# board_1_5_FixMosfetGND_OUT12V_v.net
KiCad netlist of a schematic drawn in EAGLE
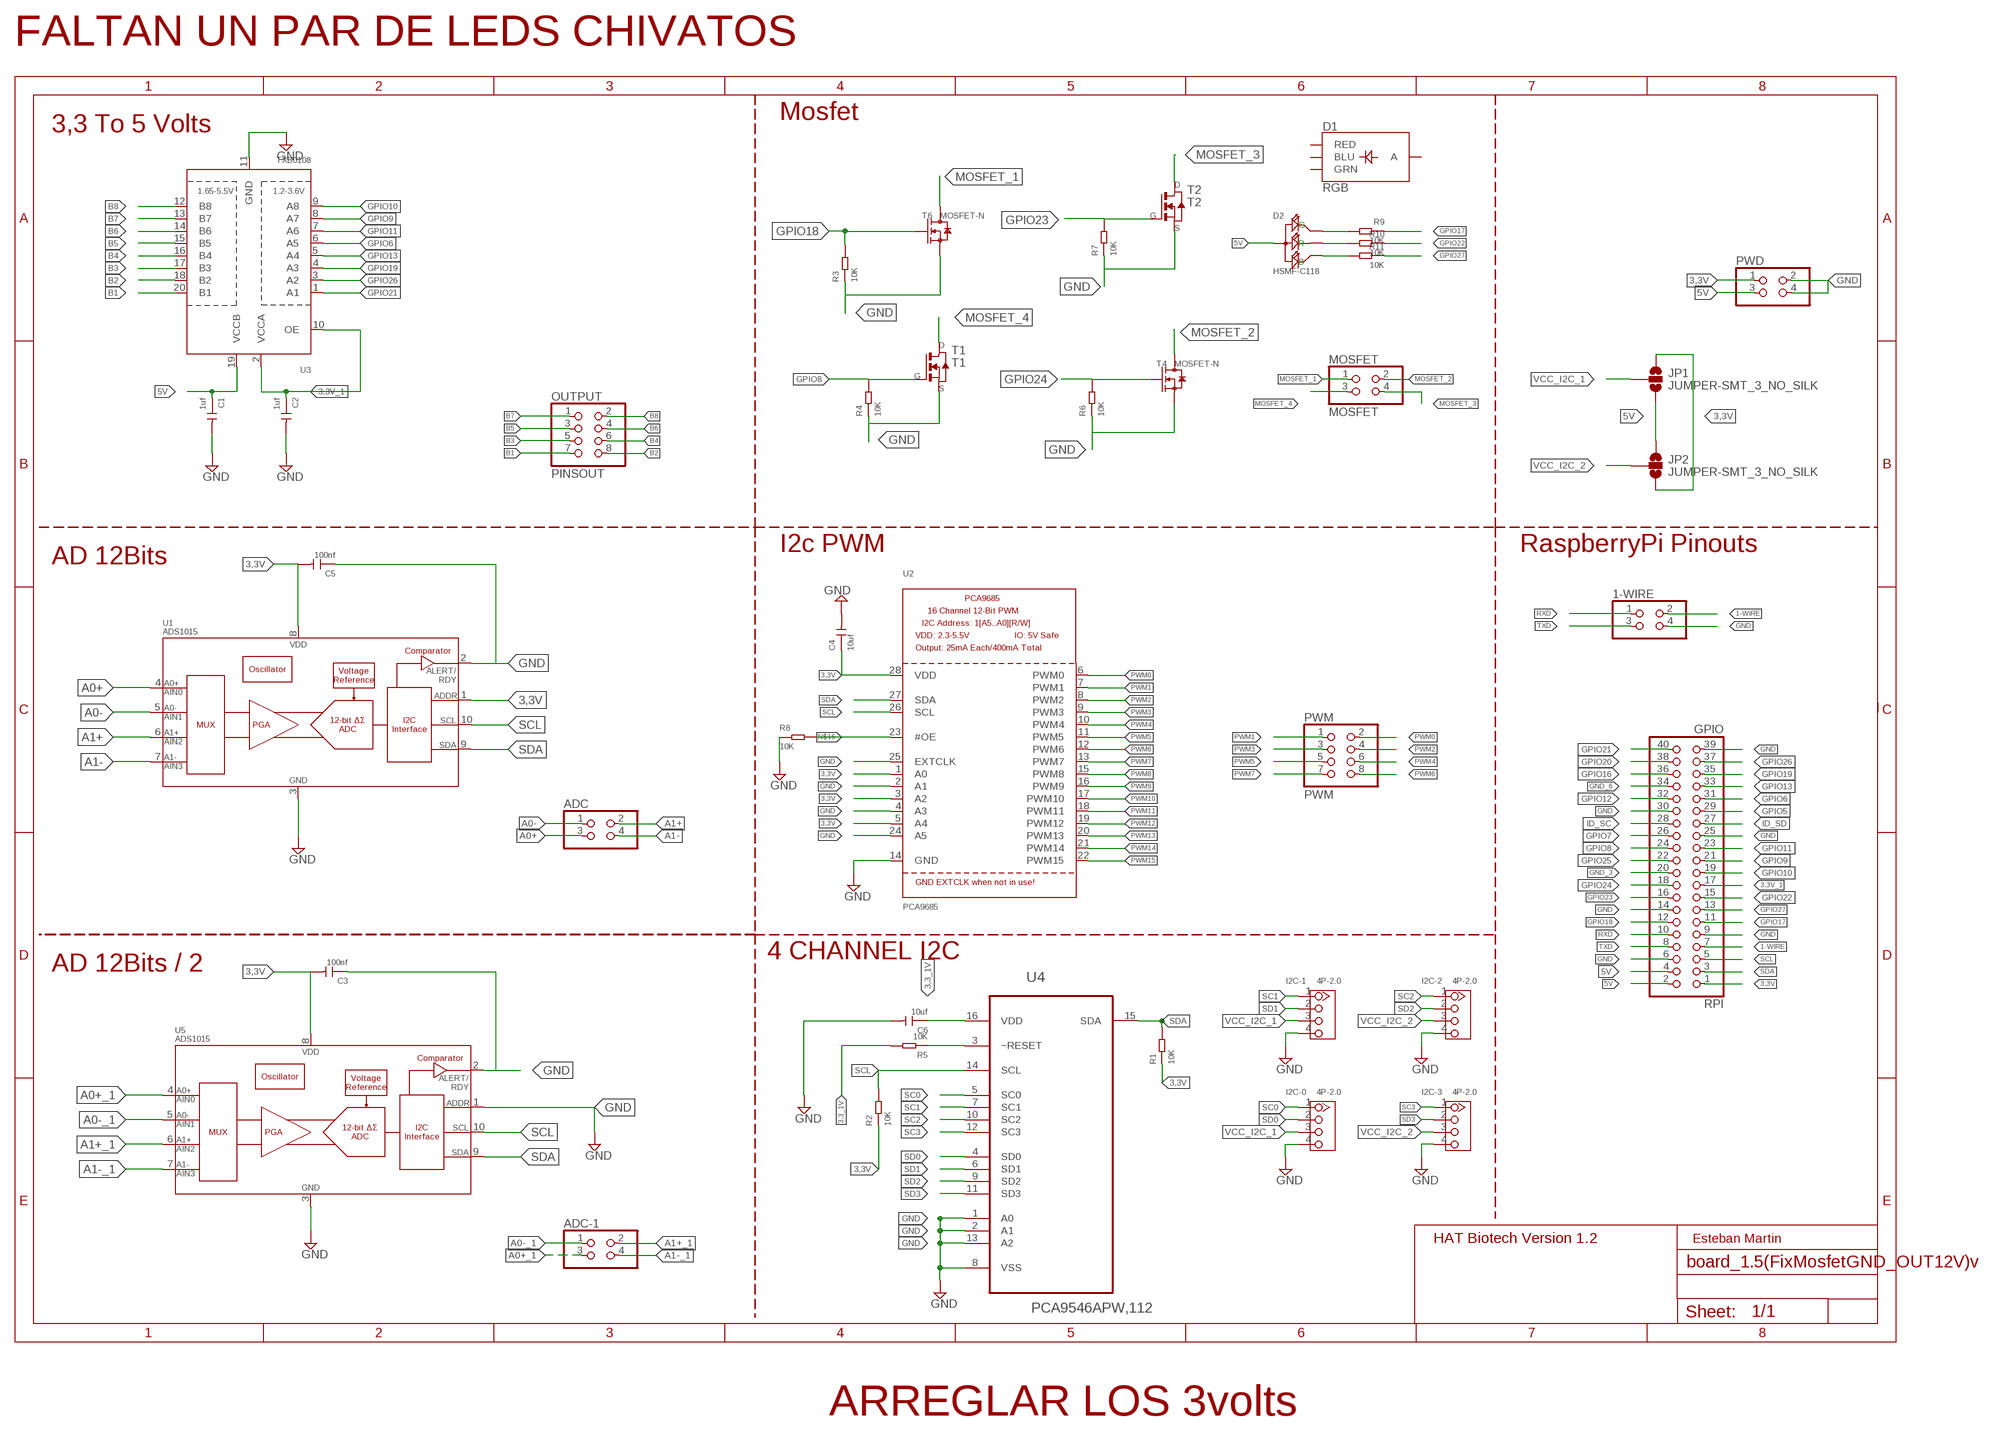
[diagram p0: schematic, sheet 1]

(export (version "E")
  (design (tool "Eeschema 10.0.6"))
  (components
    (comp (ref "1-WIRE")
      (value "PINHD-2X2")
      (footprint "eagle-import:2X02")
      (libsource (lib "eagle-import") (part "PINHD-2X2"))
    )
    (comp (ref "ADC")
      (value "PINHD-2X2")
      (footprint "eagle-import:2X02")
      (libsource (lib "eagle-import") (part "PINHD-2X2"))
    )
    (comp (ref "ADC-1")
      (value "PINHD-2X2")
      (footprint "eagle-import:2X02")
      (libsource (lib "eagle-import") (part "PINHD-2X2"))
    )
    (comp (ref "C1")
      (value "1uf")
      (footprint "eagle-import:C0805")
      (fields (field (name "MPN") "CC0805KKX7R8BB105"))
      (libsource (lib "eagle-import") (part "CERAMIC-1UF-25V-10%-X7R(0805)"))
    )
    (comp (ref "C2")
      (value "1uf")
      (footprint "eagle-import:C0805")
      (fields (field (name "MPN") "CC0805KKX7R8BB105"))
      (libsource (lib "eagle-import") (part "CERAMIC-1UF-25V-10%-X7R(0805)"))
    )
    (comp (ref "C3")
      (value "100nf")
      (footprint "eagle-import:C0805")
      (fields (field (name "MPN") "CC0805KRX7R9BB104"))
      (libsource (lib "eagle-import") (part "CERAMIC-100NF-50V-10%-X7R(0805)"))
    )
    (comp (ref "C4")
      (value "10uf")
      (footprint "eagle-import:C0805")
      (fields (field (name "MPN") "CC0805KKX7R8BB105"))
      (libsource (lib "eagle-import") (part "CERAMIC-1UF-25V-10%-X7R(0805)"))
    )
    (comp (ref "C5")
      (value "100nf")
      (footprint "eagle-import:C0805")
      (fields (field (name "MPN") "CC0805KRX7R9BB104"))
      (libsource (lib "eagle-import") (part "CERAMIC-100NF-50V-10%-X7R(0805)"))
    )
    (comp (ref "C6")
      (value "10uf")
      (footprint "eagle-import:C0805")
      (fields (field (name "MPN") "CC0805KKX7R8BB105"))
      (libsource (lib "eagle-import") (part "CERAMIC-1UF-25V-10%-X7R(0805)"))
    )
    (comp (ref "D1")
      (value "RGB")
      (footprint "eagle-import:P-LCC-4-3")
      (libsource (lib "eagle-import") (part "LED-RGB-CAPLCC"))
    )
    (comp (ref "D2")
      (value "HSMF-C118")
      (footprint "eagle-import:LED4-SMD-1210")
      (libsource (lib "eagle-import") (part "SMD-LED-RGB(4P-1210)"))
    )
    (comp (ref "I2C-0")
      (value "4P-2.0")
      (footprint "eagle-import:HW4-2.0")
      (libsource (lib "eagle-import") (part "GROVE-CONNECTOR-DIP(4P-2.0)"))
    )
    (comp (ref "I2C-1")
      (value "4P-2.0")
      (footprint "eagle-import:HW4-2.0")
      (libsource (lib "eagle-import") (part "GROVE-CONNECTOR-DIP(4P-2.0)"))
    )
    (comp (ref "I2C-2")
      (value "4P-2.0")
      (footprint "eagle-import:HW4-2.0")
      (libsource (lib "eagle-import") (part "GROVE-CONNECTOR-DIP(4P-2.0)"))
    )
    (comp (ref "I2C-3")
      (value "4P-2.0")
      (footprint "eagle-import:HW4-2.0")
      (libsource (lib "eagle-import") (part "GROVE-CONNECTOR-DIP(4P-2.0)"))
    )
    (comp (ref "JP1")
      (value "JUMPER-SMT_3_NO_SILK")
      (footprint "eagle-import:SMT-JUMPER_3_NO_SILK")
      (libsource (lib "eagle-import") (part "JUMPER-SMT_3_NO_SILK"))
    )
    (comp (ref "JP2")
      (value "JUMPER-SMT_3_NO_SILK")
      (footprint "eagle-import:SMT-JUMPER_3_NO_SILK")
      (libsource (lib "eagle-import") (part "JUMPER-SMT_3_NO_SILK"))
    )
    (comp (ref "MOSFET")
      (value "MOSFET")
      (footprint "eagle-import:2X02")
      (libsource (lib "eagle-import") (part "PINHD-2X2"))
    )
    (comp (ref "OUTPUT")
      (value "PINSOUT")
      (footprint "eagle-import:2X04")
      (libsource (lib "eagle-import") (part "PINHD-2X4"))
    )
    (comp (ref "PWD")
      (value "PINHD-2X2")
      (footprint "eagle-import:2X02")
      (libsource (lib "eagle-import") (part "PINHD-2X2"))
    )
    (comp (ref "PWM")
      (value "PWM")
      (footprint "eagle-import:2X04")
      (libsource (lib "eagle-import") (part "PINHD-2X4"))
    )
    (comp (ref "R1")
      (value "10K")
      (footprint "eagle-import:R0805")
      (fields (field (name "MPN") "RC0805FR-0710KL"))
      (libsource (lib "eagle-import") (part "SMD-RES-10K-1%-1/8W(0805)"))
    )
    (comp (ref "R2")
      (value "10K")
      (footprint "eagle-import:R0805")
      (fields (field (name "MPN") "RC0805FR-0710KL"))
      (libsource (lib "eagle-import") (part "SMD-RES-10K-1%-1/8W(0805)"))
    )
    (comp (ref "R3")
      (value "10K")
      (footprint "eagle-import:R0805")
      (fields (field (name "MPN") "RC0805FR-0710KL"))
      (libsource (lib "eagle-import") (part "SMD-RES-10K-1%-1/8W(0805)"))
    )
    (comp (ref "R4")
      (value "10K")
      (footprint "eagle-import:R0805")
      (fields (field (name "MPN") "RC0805FR-0710KL"))
      (libsource (lib "eagle-import") (part "SMD-RES-10K-1%-1/8W(0805)"))
    )
    (comp (ref "R5")
      (value "10K")
      (footprint "eagle-import:R0805")
      (fields (field (name "MPN") "RC0805FR-0710KL"))
      (libsource (lib "eagle-import") (part "SMD-RES-10K-1%-1/8W(0805)"))
    )
    (comp (ref "R6")
      (value "10K")
      (footprint "eagle-import:R0805")
      (fields (field (name "MPN") "RC0805FR-0710KL"))
      (libsource (lib "eagle-import") (part "SMD-RES-10K-1%-1/8W(0805)"))
    )
    (comp (ref "R7")
      (value "10K")
      (footprint "eagle-import:R0805")
      (fields (field (name "MPN") "RC0805FR-0710KL"))
      (libsource (lib "eagle-import") (part "SMD-RES-10K-1%-1/8W(0805)"))
    )
    (comp (ref "R8")
      (value "10K")
      (footprint "eagle-import:R0805")
      (fields (field (name "MPN") "RC0805FR-0710KL"))
      (libsource (lib "eagle-import") (part "SMD-RES-10K-1%-1/8W(0805)"))
    )
    (comp (ref "R9")
      (value "10K")
      (footprint "eagle-import:R0805")
      (fields (field (name "MPN") "RC0805FR-0710KL"))
      (libsource (lib "eagle-import") (part "SMD-RES-10K-1%-1/8W(0805)"))
    )
    (comp (ref "R10")
      (value "10K")
      (footprint "eagle-import:R0805")
      (fields (field (name "MPN") "RC0805FR-0710KL"))
      (libsource (lib "eagle-import") (part "SMD-RES-10K-1%-1/8W(0805)"))
    )
    (comp (ref "R11")
      (value "10K")
      (footprint "eagle-import:R0805")
      (fields (field (name "MPN") "RC0805FR-0710KL"))
      (libsource (lib "eagle-import") (part "SMD-RES-10K-1%-1/8W(0805)"))
    )
    (comp (ref "RPI")
      (value "GPIO")
      (footprint "eagle-import:2X20")
      (libsource (lib "eagle-import") (part "PINHD-2X20"))
    )
    (comp (ref "T1")
      (value "T1")
      (footprint "eagle-import:TO252")
      (libsource (lib "eagle-import") (part "NMOSFETTO252"))
    )
    (comp (ref "T2")
      (value "T2")
      (footprint "eagle-import:TO252")
      (libsource (lib "eagle-import") (part "NMOSFETTO252"))
    )
    (comp (ref "T4")
      (value "MOSFET-N")
      (footprint "eagle-import:SOT-23")
      (libsource (lib "eagle-import") (part "MOSFET-N"))
    )
    (comp (ref "T6")
      (value "MOSFET-N")
      (footprint "eagle-import:SOT-23")
      (libsource (lib "eagle-import") (part "MOSFET-N"))
    )
    (comp (ref "U1")
      (value "ADS1015")
      (footprint "eagle-import:MSOP10")
      (libsource (lib "eagle-import") (part "ADS1015"))
    )
    (comp (ref "U2")
      (value "PCA9685")
      (footprint "eagle-import:TSSOP28")
      (libsource (lib "eagle-import") (part "PCA9685"))
    )
    (comp (ref "U3")
      (value "TXB0108")
      (footprint "eagle-import:TSSOP20")
      (libsource (lib "eagle-import") (part "TXB0108PWR"))
    )
    (comp (ref "U4")
      (value "PCA9546APW,112")
      (footprint "eagle-import:SOP65P640X110-16N")
      (libsource (lib "eagle-import") (part "PCA9546APW,112"))
    )
    (comp (ref "U5")
      (value "ADS1015")
      (footprint "eagle-import:MSOP10")
      (libsource (lib "eagle-import") (part "ADS1015"))
    )
  )
  (nets
    (net (code "1") (name "1-WIRE") (class "Default")
      (node (ref "1-WIRE") (pin "2") (pinfunction "2_2") (pintype "passive"))
      (node (ref "RPI") (pin "7") (pinfunction "7_7") (pintype "passive"))
    )
    (net (code "2") (name "3,3V") (class "Default")
      (node (ref "C3") (pin "2") (pinfunction "2_2") (pintype "passive"))
      (node (ref "C4") (pin "1") (pinfunction "1_1") (pintype "passive"))
      (node (ref "C5") (pin "2") (pinfunction "2_2") (pintype "passive"))
      (node (ref "JP1") (pin "1") (pinfunction "1_1") (pintype "passive"))
      (node (ref "JP2") (pin "3") (pinfunction "3_3") (pintype "passive"))
      (node (ref "PWD") (pin "1") (pinfunction "1_1") (pintype "passive"))
      (node (ref "R1") (pin "1") (pinfunction "1_1") (pintype "passive"))
      (node (ref "R2") (pin "1") (pinfunction "1_1") (pintype "passive"))
      (node (ref "RPI") (pin "1") (pinfunction "1_1") (pintype "passive"))
      (node (ref "U1") (pin "1") (pinfunction "ADDR_1") (pintype "bidirectional"))
      (node (ref "U1") (pin "8") (pinfunction "VDD_8") (pintype "bidirectional"))
      (node (ref "U2") (pin "1") (pinfunction "A0_1") (pintype "bidirectional"))
      (node (ref "U2") (pin "28") (pinfunction "VDD_28") (pintype "power_in"))
      (node (ref "U2") (pin "3") (pinfunction "A2_3") (pintype "bidirectional"))
      (node (ref "U2") (pin "5") (pinfunction "A4_5") (pintype "bidirectional"))
      (node (ref "U5") (pin "8") (pinfunction "VDD_8") (pintype "bidirectional"))
    )
    (net (code "3") (name "3,3V_1") (class "Default")
      (node (ref "C2") (pin "1") (pinfunction "1_1") (pintype "passive"))
      (node (ref "RPI") (pin "17") (pinfunction "17_17") (pintype "passive"))
      (node (ref "U3") (pin "10") (pinfunction "OE_10") (pintype "bidirectional"))
      (node (ref "U3") (pin "2") (pinfunction "VCCA_2") (pintype "bidirectional"))
    )
    (net (code "4") (name "3,3_1V") (class "Default")
      (node (ref "C6") (pin "1") (pinfunction "1_1") (pintype "passive"))
      (node (ref "R5") (pin "2") (pinfunction "2_2") (pintype "passive"))
      (node (ref "U4") (pin "16") (pinfunction "VDD_16") (pintype "power_in"))
    )
    (net (code "5") (name "5V") (class "Default")
      (node (ref "C1") (pin "1") (pinfunction "1_1") (pintype "passive"))
      (node (ref "D2") (pin "1") (pinfunction "+_1") (pintype "bidirectional"))
      (node (ref "JP1") (pin "3") (pinfunction "3_3") (pintype "passive"))
      (node (ref "JP2") (pin "1") (pinfunction "1_1") (pintype "passive"))
      (node (ref "PWD") (pin "3") (pinfunction "3_3") (pintype "passive"))
      (node (ref "RPI") (pin "2") (pinfunction "2_2") (pintype "passive"))
      (node (ref "RPI") (pin "4") (pinfunction "4_4") (pintype "passive"))
      (node (ref "U3") (pin "19") (pinfunction "VCCB_19") (pintype "bidirectional"))
    )
    (net (code "6") (name "A0+") (class "Default")
      (node (ref "ADC") (pin "3") (pinfunction "3_3") (pintype "passive"))
      (node (ref "U1") (pin "4") (pinfunction "AIN0_4") (pintype "bidirectional"))
    )
    (net (code "7") (name "A0+_1") (class "Default")
      (node (ref "ADC-1") (pin "3") (pinfunction "3_3") (pintype "passive"))
      (node (ref "U5") (pin "4") (pinfunction "AIN0_4") (pintype "bidirectional"))
    )
    (net (code "8") (name "A0-") (class "Default")
      (node (ref "ADC") (pin "1") (pinfunction "1_1") (pintype "passive"))
      (node (ref "U1") (pin "5") (pinfunction "AIN1_5") (pintype "bidirectional"))
    )
    (net (code "9") (name "A0-_1") (class "Default")
      (node (ref "ADC-1") (pin "1") (pinfunction "1_1") (pintype "passive"))
      (node (ref "U5") (pin "5") (pinfunction "AIN1_5") (pintype "bidirectional"))
    )
    (net (code "10") (name "A1+") (class "Default")
      (node (ref "ADC") (pin "2") (pinfunction "2_2") (pintype "passive"))
      (node (ref "U1") (pin "6") (pinfunction "AIN2_6") (pintype "bidirectional"))
    )
    (net (code "11") (name "A1+_1") (class "Default")
      (node (ref "ADC-1") (pin "2") (pinfunction "2_2") (pintype "passive"))
      (node (ref "U5") (pin "6") (pinfunction "AIN2_6") (pintype "bidirectional"))
    )
    (net (code "12") (name "A1-") (class "Default")
      (node (ref "ADC") (pin "4") (pinfunction "4_4") (pintype "passive"))
      (node (ref "U1") (pin "7") (pinfunction "AIN3_7") (pintype "bidirectional"))
    )
    (net (code "13") (name "A1-_1") (class "Default")
      (node (ref "ADC-1") (pin "4") (pinfunction "4_4") (pintype "passive"))
      (node (ref "U5") (pin "7") (pinfunction "AIN3_7") (pintype "bidirectional"))
    )
    (net (code "14") (name "B1") (class "Default")
      (node (ref "OUTPUT") (pin "7") (pinfunction "7_7") (pintype "passive"))
      (node (ref "U3") (pin "20") (pinfunction "B1_20") (pintype "bidirectional"))
    )
    (net (code "15") (name "B2") (class "Default")
      (node (ref "OUTPUT") (pin "8") (pinfunction "8_8") (pintype "passive"))
      (node (ref "U3") (pin "18") (pinfunction "B2_18") (pintype "bidirectional"))
    )
    (net (code "16") (name "B3") (class "Default")
      (node (ref "OUTPUT") (pin "5") (pinfunction "5_5") (pintype "passive"))
      (node (ref "U3") (pin "17") (pinfunction "B3_17") (pintype "bidirectional"))
    )
    (net (code "17") (name "B4") (class "Default")
      (node (ref "OUTPUT") (pin "6") (pinfunction "6_6") (pintype "passive"))
      (node (ref "U3") (pin "16") (pinfunction "B4_16") (pintype "bidirectional"))
    )
    (net (code "18") (name "B5") (class "Default")
      (node (ref "OUTPUT") (pin "3") (pinfunction "3_3") (pintype "passive"))
      (node (ref "U3") (pin "15") (pinfunction "B5_15") (pintype "bidirectional"))
    )
    (net (code "19") (name "B6") (class "Default")
      (node (ref "OUTPUT") (pin "4") (pinfunction "4_4") (pintype "passive"))
      (node (ref "U3") (pin "14") (pinfunction "B6_14") (pintype "bidirectional"))
    )
    (net (code "20") (name "B7") (class "Default")
      (node (ref "OUTPUT") (pin "1") (pinfunction "1_1") (pintype "passive"))
      (node (ref "U3") (pin "13") (pinfunction "B7_13") (pintype "bidirectional"))
    )
    (net (code "21") (name "B8") (class "Default")
      (node (ref "OUTPUT") (pin "2") (pinfunction "2_2") (pintype "passive"))
      (node (ref "U3") (pin "12") (pinfunction "B8_12") (pintype "bidirectional"))
    )
    (net (code "22") (name "GND") (class "Default")
      (node (ref "1-WIRE") (pin "4") (pinfunction "4_4") (pintype "passive"))
      (node (ref "C1") (pin "2") (pinfunction "2_2") (pintype "passive"))
      (node (ref "C2") (pin "2") (pinfunction "2_2") (pintype "passive"))
      (node (ref "C3") (pin "1") (pinfunction "1_1") (pintype "passive"))
      (node (ref "C4") (pin "2") (pinfunction "2_2") (pintype "passive"))
      (node (ref "C5") (pin "1") (pinfunction "1_1") (pintype "passive"))
      (node (ref "C6") (pin "2") (pinfunction "2_2") (pintype "passive"))
      (node (ref "I2C-0") (pin "4") (pinfunction "4_4") (pintype "bidirectional"))
      (node (ref "I2C-1") (pin "4") (pinfunction "4_4") (pintype "bidirectional"))
      (node (ref "I2C-2") (pin "4") (pinfunction "4_4") (pintype "bidirectional"))
      (node (ref "I2C-3") (pin "4") (pinfunction "4_4") (pintype "bidirectional"))
      (node (ref "PWD") (pin "2") (pinfunction "2_2") (pintype "passive"))
      (node (ref "PWD") (pin "4") (pinfunction "4_4") (pintype "passive"))
      (node (ref "R3") (pin "1") (pinfunction "1_1") (pintype "passive"))
      (node (ref "R4") (pin "1") (pinfunction "1_1") (pintype "passive"))
      (node (ref "R6") (pin "1") (pinfunction "1_1") (pintype "passive"))
      (node (ref "R7") (pin "1") (pinfunction "1_1") (pintype "passive"))
      (node (ref "R8") (pin "1") (pinfunction "1_1") (pintype "passive"))
      (node (ref "RPI") (pin "14") (pinfunction "14_14") (pintype "passive"))
      (node (ref "RPI") (pin "25") (pinfunction "25_25") (pintype "passive"))
      (node (ref "RPI") (pin "30") (pinfunction "30_30") (pintype "passive"))
      (node (ref "RPI") (pin "39") (pinfunction "39_39") (pintype "passive"))
      (node (ref "RPI") (pin "6") (pinfunction "6_6") (pintype "passive"))
      (node (ref "RPI") (pin "9") (pinfunction "9_9") (pintype "passive"))
      (node (ref "T1") (pin "2") (pinfunction "S_2") (pintype "passive"))
      (node (ref "T2") (pin "2") (pinfunction "S_2") (pintype "passive"))
      (node (ref "T4") (pin "2") (pinfunction "S_2") (pintype "passive"))
      (node (ref "T6") (pin "2") (pinfunction "S_2") (pintype "passive"))
      (node (ref "U1") (pin "2") (pinfunction "ALERT/RDY_2") (pintype "bidirectional"))
      (node (ref "U1") (pin "3") (pinfunction "VSS_3") (pintype "bidirectional"))
      (node (ref "U2") (pin "14") (pinfunction "GND_14") (pintype "power_in"))
      (node (ref "U2") (pin "2") (pinfunction "A1_2") (pintype "bidirectional"))
      (node (ref "U2") (pin "24") (pinfunction "A5_24") (pintype "bidirectional"))
      (node (ref "U2") (pin "25") (pinfunction "EXTCLK_25") (pintype "input"))
      (node (ref "U2") (pin "4") (pinfunction "A3_4") (pintype "bidirectional"))
      (node (ref "U3") (pin "11") (pinfunction "GND_11") (pintype "bidirectional"))
      (node (ref "U4") (pin "1") (pinfunction "A0_1") (pintype "input"))
      (node (ref "U4") (pin "13") (pinfunction "A2_13") (pintype "input"))
      (node (ref "U4") (pin "2") (pinfunction "A1_2") (pintype "input"))
      (node (ref "U4") (pin "8") (pinfunction "VSS_8") (pintype "passive"))
      (node (ref "U5") (pin "1") (pinfunction "ADDR_1") (pintype "bidirectional"))
      (node (ref "U5") (pin "2") (pinfunction "ALERT/RDY_2") (pintype "bidirectional"))
      (node (ref "U5") (pin "3") (pinfunction "VSS_3") (pintype "bidirectional"))
    )
    (net (code "23") (name "GND_3") (class "Default")
      (node (ref "RPI") (pin "20") (pinfunction "20_20") (pintype "passive"))
    )
    (net (code "24") (name "GND_6") (class "Default")
      (node (ref "RPI") (pin "34") (pinfunction "34_34") (pintype "passive"))
    )
    (net (code "25") (name "GPIO5") (class "Default")
      (node (ref "RPI") (pin "29") (pinfunction "29_29") (pintype "passive"))
    )
    (net (code "26") (name "GPIO6") (class "Default")
      (node (ref "RPI") (pin "31") (pinfunction "31_31") (pintype "passive"))
      (node (ref "U3") (pin "6") (pinfunction "A5_6") (pintype "bidirectional"))
    )
    (net (code "27") (name "GPIO7") (class "Default")
      (node (ref "RPI") (pin "26") (pinfunction "26_26") (pintype "passive"))
    )
    (net (code "28") (name "GPIO8") (class "Default")
      (node (ref "R4") (pin "2") (pinfunction "2_2") (pintype "passive"))
      (node (ref "RPI") (pin "24") (pinfunction "24_24") (pintype "passive"))
      (node (ref "T1") (pin "1") (pinfunction "G_1") (pintype "passive"))
    )
    (net (code "29") (name "GPIO9") (class "Default")
      (node (ref "RPI") (pin "21") (pinfunction "21_21") (pintype "passive"))
      (node (ref "U3") (pin "8") (pinfunction "A7_8") (pintype "bidirectional"))
    )
    (net (code "30") (name "GPIO10") (class "Default")
      (node (ref "RPI") (pin "19") (pinfunction "19_19") (pintype "passive"))
      (node (ref "U3") (pin "9") (pinfunction "A8_9") (pintype "bidirectional"))
    )
    (net (code "31") (name "GPIO11") (class "Default")
      (node (ref "RPI") (pin "23") (pinfunction "23_23") (pintype "passive"))
      (node (ref "U3") (pin "7") (pinfunction "A6_7") (pintype "bidirectional"))
    )
    (net (code "32") (name "GPIO12") (class "Default")
      (node (ref "RPI") (pin "32") (pinfunction "32_32") (pintype "passive"))
    )
    (net (code "33") (name "GPIO13") (class "Default")
      (node (ref "RPI") (pin "33") (pinfunction "33_33") (pintype "passive"))
      (node (ref "U3") (pin "5") (pinfunction "A4_5") (pintype "bidirectional"))
    )
    (net (code "34") (name "GPIO16") (class "Default")
      (node (ref "RPI") (pin "36") (pinfunction "36_36") (pintype "passive"))
    )
    (net (code "35") (name "GPIO17") (class "Default")
      (node (ref "R9") (pin "1") (pinfunction "1_1") (pintype "passive"))
      (node (ref "RPI") (pin "11") (pinfunction "11_11") (pintype "passive"))
    )
    (net (code "36") (name "GPIO18") (class "Default")
      (node (ref "R3") (pin "2") (pinfunction "2_2") (pintype "passive"))
      (node (ref "RPI") (pin "12") (pinfunction "12_12") (pintype "passive"))
      (node (ref "T6") (pin "1") (pinfunction "G_1") (pintype "passive"))
    )
    (net (code "37") (name "GPIO19") (class "Default")
      (node (ref "RPI") (pin "35") (pinfunction "35_35") (pintype "passive"))
      (node (ref "U3") (pin "4") (pinfunction "A3_4") (pintype "bidirectional"))
    )
    (net (code "38") (name "GPIO20") (class "Default")
      (node (ref "RPI") (pin "38") (pinfunction "38_38") (pintype "passive"))
    )
    (net (code "39") (name "GPIO21") (class "Default")
      (node (ref "RPI") (pin "40") (pinfunction "40_40") (pintype "passive"))
      (node (ref "U3") (pin "1") (pinfunction "A1_1") (pintype "bidirectional"))
    )
    (net (code "40") (name "GPIO22") (class "Default")
      (node (ref "R10") (pin "1") (pinfunction "1_1") (pintype "passive"))
      (node (ref "RPI") (pin "15") (pinfunction "15_15") (pintype "passive"))
    )
    (net (code "41") (name "GPIO23") (class "Default")
      (node (ref "R7") (pin "2") (pinfunction "2_2") (pintype "passive"))
      (node (ref "RPI") (pin "16") (pinfunction "16_16") (pintype "passive"))
      (node (ref "T2") (pin "1") (pinfunction "G_1") (pintype "passive"))
    )
    (net (code "42") (name "GPIO24") (class "Default")
      (node (ref "R6") (pin "2") (pinfunction "2_2") (pintype "passive"))
      (node (ref "RPI") (pin "18") (pinfunction "18_18") (pintype "passive"))
      (node (ref "T4") (pin "1") (pinfunction "G_1") (pintype "passive"))
    )
    (net (code "43") (name "GPIO25") (class "Default")
      (node (ref "RPI") (pin "22") (pinfunction "22_22") (pintype "passive"))
    )
    (net (code "44") (name "GPIO26") (class "Default")
      (node (ref "RPI") (pin "37") (pinfunction "37_37") (pintype "passive"))
      (node (ref "U3") (pin "3") (pinfunction "A2_3") (pintype "bidirectional"))
    )
    (net (code "45") (name "GPIO27") (class "Default")
      (node (ref "R11") (pin "1") (pinfunction "1_1") (pintype "passive"))
      (node (ref "RPI") (pin "13") (pinfunction "13_13") (pintype "passive"))
    )
    (net (code "46") (name "ID_SC") (class "Default")
      (node (ref "RPI") (pin "28") (pinfunction "28_28") (pintype "passive"))
    )
    (net (code "47") (name "ID_SD") (class "Default")
      (node (ref "RPI") (pin "27") (pinfunction "27_27") (pintype "passive"))
    )
    (net (code "48") (name "MOSFET_1") (class "Default")
      (node (ref "MOSFET") (pin "1") (pinfunction "1_1") (pintype "passive"))
      (node (ref "T6") (pin "3") (pinfunction "D_3") (pintype "passive"))
    )
    (net (code "49") (name "MOSFET_2") (class "Default")
      (node (ref "MOSFET") (pin "2") (pinfunction "2_2") (pintype "passive"))
      (node (ref "T4") (pin "3") (pinfunction "D_3") (pintype "passive"))
    )
    (net (code "50") (name "MOSFET_3") (class "Default")
      (node (ref "MOSFET") (pin "4") (pinfunction "4_4") (pintype "passive"))
      (node (ref "T2") (pin "3") (pinfunction "D_3") (pintype "passive"))
    )
    (net (code "51") (name "MOSFET_4") (class "Default")
      (node (ref "MOSFET") (pin "3") (pinfunction "3_3") (pintype "passive"))
      (node (ref "T1") (pin "3") (pinfunction "D_3") (pintype "passive"))
    )
    (net (code "52") (name "N$16") (class "Default")
      (node (ref "R8") (pin "2") (pinfunction "2_2") (pintype "passive"))
      (node (ref "U2") (pin "23") (pinfunction "#OE_23") (pintype "input"))
    )
    (net (code "53") (name "Net-(D2-B)") (class "Default")
      (node (ref "D2") (pin "4") (pinfunction "B_4") (pintype "bidirectional"))
      (node (ref "R11") (pin "2") (pinfunction "2_2") (pintype "passive"))
    )
    (net (code "54") (name "Net-(D2-G)") (class "Default")
      (node (ref "D2") (pin "3") (pinfunction "G_3") (pintype "bidirectional"))
      (node (ref "R9") (pin "2") (pinfunction "2_2") (pintype "passive"))
    )
    (net (code "55") (name "Net-(D2-R)") (class "Default")
      (node (ref "D2") (pin "2") (pinfunction "R_2") (pintype "bidirectional"))
      (node (ref "R10") (pin "2") (pinfunction "2_2") (pintype "passive"))
    )
    (net (code "56") (name "Net-(U4-~{RESET})") (class "Default")
      (node (ref "R5") (pin "1") (pinfunction "1_1") (pintype "passive"))
      (node (ref "U4") (pin "3") (pinfunction "~{RESET}_3") (pintype "input"))
    )
    (net (code "57") (name "PWM0") (class "Default")
      (node (ref "PWM") (pin "2") (pinfunction "2_2") (pintype "passive"))
      (node (ref "U2") (pin "6") (pinfunction "PWM0_6") (pintype "output"))
    )
    (net (code "58") (name "PWM1") (class "Default")
      (node (ref "PWM") (pin "1") (pinfunction "1_1") (pintype "passive"))
      (node (ref "U2") (pin "7") (pinfunction "PWM1_7") (pintype "output"))
    )
    (net (code "59") (name "PWM2") (class "Default")
      (node (ref "PWM") (pin "4") (pinfunction "4_4") (pintype "passive"))
      (node (ref "U2") (pin "8") (pinfunction "PWM2_8") (pintype "output"))
    )
    (net (code "60") (name "PWM3") (class "Default")
      (node (ref "PWM") (pin "3") (pinfunction "3_3") (pintype "passive"))
      (node (ref "U2") (pin "9") (pinfunction "PWM3_9") (pintype "output"))
    )
    (net (code "61") (name "PWM4") (class "Default")
      (node (ref "PWM") (pin "6") (pinfunction "6_6") (pintype "passive"))
      (node (ref "U2") (pin "10") (pinfunction "PWM4_10") (pintype "output"))
    )
    (net (code "62") (name "PWM5") (class "Default")
      (node (ref "PWM") (pin "5") (pinfunction "5_5") (pintype "passive"))
      (node (ref "U2") (pin "11") (pinfunction "PWM5_11") (pintype "output"))
    )
    (net (code "63") (name "PWM6") (class "Default")
      (node (ref "PWM") (pin "8") (pinfunction "8_8") (pintype "passive"))
      (node (ref "U2") (pin "12") (pinfunction "PWM6_12") (pintype "output"))
    )
    (net (code "64") (name "PWM7") (class "Default")
      (node (ref "PWM") (pin "7") (pinfunction "7_7") (pintype "passive"))
      (node (ref "U2") (pin "13") (pinfunction "PWM7_13") (pintype "output"))
    )
    (net (code "65") (name "PWM8") (class "Default")
      (node (ref "U2") (pin "15") (pinfunction "PWM8_15") (pintype "output"))
    )
    (net (code "66") (name "PWM9") (class "Default")
      (node (ref "U2") (pin "16") (pinfunction "PWM9_16") (pintype "output"))
    )
    (net (code "67") (name "PWM10") (class "Default")
      (node (ref "U2") (pin "17") (pinfunction "PWM10_17") (pintype "output"))
    )
    (net (code "68") (name "PWM11") (class "Default")
      (node (ref "U2") (pin "18") (pinfunction "PWM11_18") (pintype "output"))
    )
    (net (code "69") (name "PWM12") (class "Default")
      (node (ref "U2") (pin "19") (pinfunction "PWM12_19") (pintype "output"))
    )
    (net (code "70") (name "PWM13") (class "Default")
      (node (ref "U2") (pin "20") (pinfunction "PWM13_20") (pintype "output"))
    )
    (net (code "71") (name "PWM14") (class "Default")
      (node (ref "U2") (pin "21") (pinfunction "PWM14_21") (pintype "output"))
    )
    (net (code "72") (name "PWM15") (class "Default")
      (node (ref "U2") (pin "22") (pinfunction "PWM15_22") (pintype "output"))
    )
    (net (code "73") (name "RXD") (class "Default")
      (node (ref "1-WIRE") (pin "1") (pinfunction "1_1") (pintype "passive"))
      (node (ref "RPI") (pin "10") (pinfunction "10_10") (pintype "passive"))
    )
    (net (code "74") (name "SC0") (class "Default")
      (node (ref "I2C-0") (pin "1") (pinfunction "1_1") (pintype "bidirectional"))
      (node (ref "U4") (pin "5") (pinfunction "SC0_5") (pintype "input"))
    )
    (net (code "75") (name "SC1") (class "Default")
      (node (ref "I2C-1") (pin "1") (pinfunction "1_1") (pintype "bidirectional"))
      (node (ref "U4") (pin "7") (pinfunction "SC1_7") (pintype "input"))
    )
    (net (code "76") (name "SC2") (class "Default")
      (node (ref "I2C-2") (pin "1") (pinfunction "1_1") (pintype "bidirectional"))
      (node (ref "U4") (pin "10") (pinfunction "SC2_10") (pintype "input"))
    )
    (net (code "77") (name "SC3") (class "Default")
      (node (ref "I2C-3") (pin "1") (pinfunction "1_1") (pintype "bidirectional"))
      (node (ref "U4") (pin "12") (pinfunction "SC3_12") (pintype "input"))
    )
    (net (code "78") (name "SCL") (class "Default")
      (node (ref "R2") (pin "2") (pinfunction "2_2") (pintype "passive"))
      (node (ref "RPI") (pin "5") (pinfunction "5_5") (pintype "passive"))
      (node (ref "U1") (pin "10") (pinfunction "SCL_10") (pintype "bidirectional"))
      (node (ref "U2") (pin "26") (pinfunction "SCL_26") (pintype "bidirectional"))
      (node (ref "U4") (pin "14") (pinfunction "SCL_14") (pintype "bidirectional"))
      (node (ref "U5") (pin "10") (pinfunction "SCL_10") (pintype "bidirectional"))
    )
    (net (code "79") (name "SD0") (class "Default")
      (node (ref "I2C-0") (pin "2") (pinfunction "2_2") (pintype "bidirectional"))
      (node (ref "U4") (pin "4") (pinfunction "SD0_4") (pintype "input"))
    )
    (net (code "80") (name "SD1") (class "Default")
      (node (ref "I2C-1") (pin "2") (pinfunction "2_2") (pintype "bidirectional"))
      (node (ref "U4") (pin "6") (pinfunction "SD1_6") (pintype "input"))
    )
    (net (code "81") (name "SD2") (class "Default")
      (node (ref "I2C-2") (pin "2") (pinfunction "2_2") (pintype "bidirectional"))
      (node (ref "U4") (pin "9") (pinfunction "SD2_9") (pintype "input"))
    )
    (net (code "82") (name "SD3") (class "Default")
      (node (ref "I2C-3") (pin "2") (pinfunction "2_2") (pintype "bidirectional"))
      (node (ref "U4") (pin "11") (pinfunction "SD3_11") (pintype "input"))
    )
    (net (code "83") (name "SDA") (class "Default")
      (node (ref "R1") (pin "2") (pinfunction "2_2") (pintype "passive"))
      (node (ref "RPI") (pin "3") (pinfunction "3_3") (pintype "passive"))
      (node (ref "U1") (pin "9") (pinfunction "SDA_9") (pintype "bidirectional"))
      (node (ref "U2") (pin "27") (pinfunction "SDA_27") (pintype "bidirectional"))
      (node (ref "U4") (pin "15") (pinfunction "SDA_15") (pintype "bidirectional"))
      (node (ref "U5") (pin "9") (pinfunction "SDA_9") (pintype "bidirectional"))
    )
    (net (code "84") (name "TXD") (class "Default")
      (node (ref "1-WIRE") (pin "3") (pinfunction "3_3") (pintype "passive"))
      (node (ref "RPI") (pin "8") (pinfunction "8_8") (pintype "passive"))
    )
    (net (code "85") (name "VCC_I2C_1") (class "Default")
      (node (ref "I2C-0") (pin "3") (pinfunction "3_3") (pintype "bidirectional"))
      (node (ref "I2C-1") (pin "3") (pinfunction "3_3") (pintype "bidirectional"))
      (node (ref "JP1") (pin "2") (pinfunction "2_2") (pintype "passive"))
    )
    (net (code "86") (name "VCC_I2C_2") (class "Default")
      (node (ref "I2C-2") (pin "3") (pinfunction "3_3") (pintype "bidirectional"))
      (node (ref "I2C-3") (pin "3") (pinfunction "3_3") (pintype "bidirectional"))
      (node (ref "JP2") (pin "2") (pinfunction "2_2") (pintype "passive"))
    )
    (net (code "87") (name "unconnected-(D1-A-Pad4)") (class "Default")
      (node (ref "D1") (pin "4") (pinfunction "A_4") (pintype "bidirectional"))
    )
    (net (code "88") (name "unconnected-(D1-BLU-Pad3)") (class "Default")
      (node (ref "D1") (pin "3") (pinfunction "BLU_3") (pintype "bidirectional"))
    )
    (net (code "89") (name "unconnected-(D1-GRN-Pad2)") (class "Default")
      (node (ref "D1") (pin "2") (pinfunction "GRN_2") (pintype "bidirectional"))
    )
    (net (code "90") (name "unconnected-(D1-RED-Pad1)") (class "Default")
      (node (ref "D1") (pin "1") (pinfunction "RED_1") (pintype "bidirectional"))
    )
  )
)
